# TDA5340.net
KiCad netlist of a schematic drawn in Altium Designer
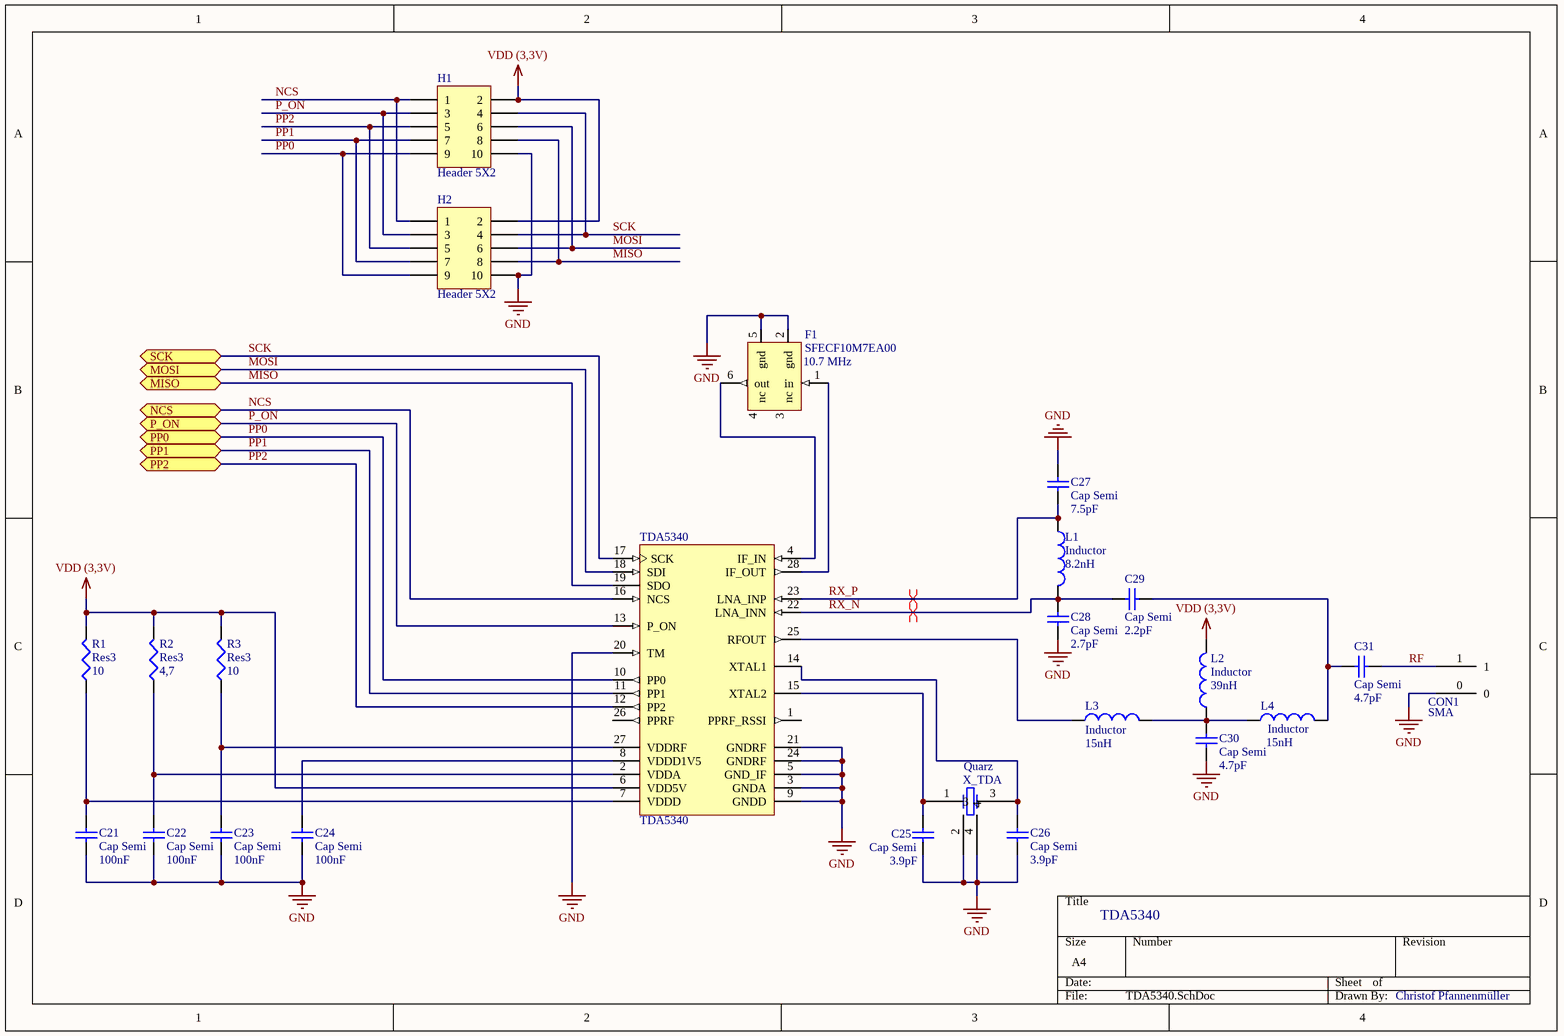
[diagram p0: TDA5340.SchDoc]

(export (version "E")
  (design (tool "Eeschema 10.0.6"))
  (components
    (comp (ref "C21")
      (value "Cap Semi")
      (footprint "0402")
      (description "Capacitor (Semiconductor SIM Model)")
      (fields (field (name "ALTIUM_VALUE") "100nF") (field (name "PUBLISHER") "Altium Limited"))
      (libsource (lib "Miscellaneous Devices") (part "Cap Semi"))
    )
    (comp (ref "C22")
      (value "Cap Semi")
      (footprint "0402")
      (description "Capacitor (Semiconductor SIM Model)")
      (fields (field (name "ALTIUM_VALUE") "100nF") (field (name "PUBLISHER") "Altium Limited"))
      (libsource (lib "Miscellaneous Devices") (part "Cap Semi"))
    )
    (comp (ref "C23")
      (value "Cap Semi")
      (footprint "0402")
      (description "Capacitor (Semiconductor SIM Model)")
      (fields (field (name "ALTIUM_VALUE") "100nF") (field (name "PUBLISHER") "Altium Limited"))
      (libsource (lib "Miscellaneous Devices") (part "Cap Semi"))
    )
    (comp (ref "C24")
      (value "Cap Semi")
      (footprint "0402")
      (description "Capacitor (Semiconductor SIM Model)")
      (fields (field (name "ALTIUM_VALUE") "100nF") (field (name "PUBLISHER") "Altium Limited"))
      (libsource (lib "Miscellaneous Devices") (part "Cap Semi"))
    )
    (comp (ref "C25")
      (value "Cap Semi")
      (footprint "0402")
      (description "Capacitor (Semiconductor SIM Model)")
      (fields (field (name "ALTIUM_VALUE") "3.9pF") (field (name "PUBLISHER") "Altium Limited"))
      (libsource (lib "Miscellaneous Devices") (part "Cap Semi"))
    )
    (comp (ref "C26")
      (value "Cap Semi")
      (footprint "0402")
      (description "Capacitor (Semiconductor SIM Model)")
      (fields (field (name "ALTIUM_VALUE") "3.9pF") (field (name "PUBLISHER") "Altium Limited"))
      (libsource (lib "Miscellaneous Devices") (part "Cap Semi"))
    )
    (comp (ref "C27")
      (value "Cap Semi")
      (footprint "0402")
      (description "Capacitor (Semiconductor SIM Model)")
      (fields (field (name "ALTIUM_VALUE") "7.5pF") (field (name "PUBLISHER") "Altium Limited"))
      (libsource (lib "Miscellaneous Devices") (part "Cap Semi"))
    )
    (comp (ref "C28")
      (value "Cap Semi")
      (footprint "0402")
      (description "Capacitor (Semiconductor SIM Model)")
      (fields (field (name "ALTIUM_VALUE") "2.7pF") (field (name "PUBLISHER") "Altium Limited"))
      (libsource (lib "Miscellaneous Devices") (part "Cap Semi"))
    )
    (comp (ref "C29")
      (value "Cap Semi")
      (footprint "0402")
      (description "Capacitor (Semiconductor SIM Model)")
      (fields (field (name "ALTIUM_VALUE") "2.2pF") (field (name "PUBLISHER") "Altium Limited"))
      (libsource (lib "Miscellaneous Devices") (part "Cap Semi"))
    )
    (comp (ref "C30")
      (value "Cap Semi")
      (footprint "0402")
      (description "Capacitor (Semiconductor SIM Model)")
      (fields (field (name "ALTIUM_VALUE") "4.7pF") (field (name "PUBLISHER") "Altium Limited"))
      (libsource (lib "Miscellaneous Devices") (part "Cap Semi"))
    )
    (comp (ref "C31")
      (value "Cap Semi")
      (footprint "0402")
      (description "Capacitor (Semiconductor SIM Model)")
      (fields (field (name "ALTIUM_VALUE") "4.7pF") (field (name "PUBLISHER") "Altium Limited"))
      (libsource (lib "Miscellaneous Devices") (part "Cap Semi"))
    )
    (comp (ref "CON1") (value "SMA") (footprint "SMA") (libsource (lib "Schlib1_rev2") (part "SMA")))
    (comp (ref "F1")
      (value "SFECF10M7EA00")
      (footprint "SOP6")
      (fields (field (name "FREQUENZ") "10.7 MHz"))
      (libsource (lib "Schlib1") (part "SFECF10M7EA00"))
    )
    (comp (ref "H1")
      (value "Header 5X2")
      (footprint "HDR2X5")
      (description "Header, 5-Pin, Dual row")
      (fields (field (name "PUBLISHER") "Altium Limited"))
      (libsource (lib "Miscellaneous Connectors") (part "Header 5X2"))
    )
    (comp (ref "H2")
      (value "Header 5X2")
      (footprint "HDR2X5")
      (description "Header, 5-Pin, Dual row")
      (fields (field (name "PUBLISHER") "Altium Limited"))
      (libsource (lib "Miscellaneous Connectors") (part "Header 5X2"))
    )
    (comp (ref "L1")
      (value "Inductor")
      (footprint "INDC1608L")
      (fields (field (name "ALTIUM_VALUE") "8.2nH") (field (name "PUBLISHER") "Altium Limited"))
      (libsource (lib "Miscellaneous Devices") (part "Inductor"))
    )
    (comp (ref "L2")
      (value "Inductor")
      (footprint "INDC1608L")
      (fields (field (name "ALTIUM_VALUE") "39nH") (field (name "PUBLISHER") "Altium Limited"))
      (libsource (lib "Miscellaneous Devices") (part "Inductor"))
    )
    (comp (ref "L3")
      (value "Inductor")
      (footprint "INDC1608L")
      (fields (field (name "ALTIUM_VALUE") "15nH") (field (name "PUBLISHER") "Altium Limited"))
      (libsource (lib "Miscellaneous Devices") (part "Inductor"))
    )
    (comp (ref "L4")
      (value "Inductor")
      (footprint "INDC1608L")
      (fields (field (name "ALTIUM_VALUE") "15nH") (field (name "PUBLISHER") "Altium Limited"))
      (libsource (lib "Miscellaneous Devices") (part "Inductor"))
    )
    (comp (ref "R1")
      (value "Res3")
      (footprint "J1-0603")
      (description "Resistor")
      (fields (field (name "ALTIUM_VALUE") "10") (field (name "PUBLISHER") "Altium Limited"))
      (libsource (lib "Miscellaneous Devices") (part "Res3"))
    )
    (comp (ref "R2")
      (value "Res3")
      (footprint "J1-0603")
      (description "Resistor")
      (fields (field (name "ALTIUM_VALUE") "4,7") (field (name "PUBLISHER") "Altium Limited"))
      (libsource (lib "Miscellaneous Devices") (part "Res3"))
    )
    (comp (ref "R3")
      (value "Res3")
      (footprint "J1-0603")
      (description "Resistor")
      (fields (field (name "ALTIUM_VALUE") "10") (field (name "PUBLISHER") "Altium Limited"))
      (libsource (lib "Miscellaneous Devices") (part "Res3"))
    )
    (comp (ref "TDA5340")
      (value "TDA5340")
      (footprint "INF-PG-TSSOP-28_N")
      (description "High Sensitivity Multi-Channel Transceiver, -40 to 110 degC, PG-TSSOP-28, Green")
      (fields (field (name "MANUFACTURER") "Infineon"))
      (libsource (lib "TDA5340") (part "TDA5340"))
    )
    (comp (ref "X_TDA") (value "Quarz") (footprint "Quarz") (libsource (lib "Schlib1") (part "Quarz")))
  )
  (nets
    (net (code "1") (name "/MISO") (class "Default")
      (node (ref "H1") (pin "8") (pinfunction "8_8") (pintype "passive"))
      (node (ref "H2") (pin "8") (pinfunction "8_8") (pintype "passive"))
      (node (ref "TDA5340") (pin "19") (pinfunction "SDO_19") (pintype "tri_state"))
    )
    (net (code "2") (name "/MOSI") (class "Default")
      (node (ref "H1") (pin "6") (pinfunction "6_6") (pintype "passive"))
      (node (ref "H2") (pin "6") (pinfunction "6_6") (pintype "passive"))
      (node (ref "TDA5340") (pin "18") (pinfunction "SDI_18") (pintype "input"))
    )
    (net (code "3") (name "/NCS") (class "Default")
      (node (ref "H1") (pin "1") (pinfunction "1_1") (pintype "passive"))
      (node (ref "H2") (pin "1") (pinfunction "1_1") (pintype "passive"))
      (node (ref "TDA5340") (pin "16") (pinfunction "NCS_16") (pintype "input"))
    )
    (net (code "4") (name "/PP0") (class "Default")
      (node (ref "H1") (pin "9") (pinfunction "9_9") (pintype "passive"))
      (node (ref "H2") (pin "9") (pinfunction "9_9") (pintype "passive"))
      (node (ref "TDA5340") (pin "10") (pinfunction "PP0_10") (pintype "output"))
    )
    (net (code "5") (name "/PP1") (class "Default")
      (node (ref "H1") (pin "7") (pinfunction "7_7") (pintype "passive"))
      (node (ref "H2") (pin "7") (pinfunction "7_7") (pintype "passive"))
      (node (ref "TDA5340") (pin "11") (pinfunction "PP1_11") (pintype "output"))
    )
    (net (code "6") (name "/PP2") (class "Default")
      (node (ref "H1") (pin "5") (pinfunction "5_5") (pintype "passive"))
      (node (ref "H2") (pin "5") (pinfunction "5_5") (pintype "passive"))
      (node (ref "TDA5340") (pin "12") (pinfunction "PP2_12") (pintype "output"))
    )
    (net (code "7") (name "/P_ON") (class "Default")
      (node (ref "H1") (pin "3") (pinfunction "3_3") (pintype "passive"))
      (node (ref "H2") (pin "3") (pinfunction "3_3") (pintype "passive"))
      (node (ref "TDA5340") (pin "13") (pinfunction "P_ON_13") (pintype "input"))
    )
    (net (code "8") (name "/RF") (class "Default")
      (node (ref "C31") (pin "2") (pinfunction "2_2") (pintype "passive"))
      (node (ref "CON1") (pin "1") (pinfunction "1_1") (pintype "passive"))
    )
    (net (code "9") (name "/RX_N") (class "Default")
      (node (ref "C28") (pin "1") (pinfunction "1_1") (pintype "passive"))
      (node (ref "C29") (pin "2") (pinfunction "2_2") (pintype "passive"))
      (node (ref "L1") (pin "2") (pinfunction "2_2") (pintype "passive"))
      (node (ref "TDA5340") (pin "22") (pinfunction "LNA_INN_22") (pintype "input"))
    )
    (net (code "10") (name "/RX_P") (class "Default")
      (node (ref "C27") (pin "2") (pinfunction "2_2") (pintype "passive"))
      (node (ref "L1") (pin "1") (pinfunction "1_1") (pintype "passive"))
      (node (ref "TDA5340") (pin "23") (pinfunction "LNA_INP_23") (pintype "input"))
    )
    (net (code "11") (name "/SCK") (class "Default")
      (node (ref "H1") (pin "4") (pinfunction "4_4") (pintype "passive"))
      (node (ref "H2") (pin "4") (pinfunction "4_4") (pintype "passive"))
      (node (ref "TDA5340") (pin "17") (pinfunction "SCK_17") (pintype "input"))
    )
    (net (code "12") (name "GND") (class "Default")
      (node (ref "C21") (pin "2") (pinfunction "2_2") (pintype "passive"))
      (node (ref "C22") (pin "2") (pinfunction "2_2") (pintype "passive"))
      (node (ref "C23") (pin "2") (pinfunction "2_2") (pintype "passive"))
      (node (ref "C24") (pin "2") (pinfunction "2_2") (pintype "passive"))
      (node (ref "C25") (pin "2") (pinfunction "2_2") (pintype "passive"))
      (node (ref "C26") (pin "1") (pinfunction "1_1") (pintype "passive"))
      (node (ref "C27") (pin "1") (pinfunction "1_1") (pintype "passive"))
      (node (ref "C28") (pin "2") (pinfunction "2_2") (pintype "passive"))
      (node (ref "C30") (pin "1") (pinfunction "1_1") (pintype "passive"))
      (node (ref "CON1") (pin "0") (pinfunction "0_0") (pintype "passive"))
      (node (ref "F1") (pin "2") (pinfunction "gnd_2") (pintype "power_in"))
      (node (ref "F1") (pin "5") (pinfunction "gnd_5") (pintype "passive"))
      (node (ref "H1") (pin "10") (pinfunction "10_10") (pintype "passive"))
      (node (ref "H2") (pin "10") (pinfunction "10_10") (pintype "passive"))
      (node (ref "TDA5340") (pin "20") (pinfunction "TM_20") (pintype "input"))
      (node (ref "TDA5340") (pin "21") (pinfunction "GNDRF_21") (pintype "power_in"))
      (node (ref "TDA5340") (pin "24") (pinfunction "GNDRF_24") (pintype "power_in"))
      (node (ref "TDA5340") (pin "3") (pinfunction "GNDA_3") (pintype "power_in"))
      (node (ref "TDA5340") (pin "5") (pinfunction "GND_IF_5") (pintype "power_in"))
      (node (ref "TDA5340") (pin "9") (pinfunction "GNDD_9") (pintype "power_in"))
      (node (ref "X_TDA") (pin "2") (pinfunction "2_2") (pintype "passive"))
      (node (ref "X_TDA") (pin "4") (pinfunction "4_4") (pintype "passive"))
    )
    (net (code "13") (name "Net-(C29-Pad1)") (class "Default")
      (node (ref "C29") (pin "1") (pinfunction "1_1") (pintype "passive"))
      (node (ref "C31") (pin "1") (pinfunction "1_1") (pintype "passive"))
      (node (ref "L4") (pin "2") (pinfunction "2_2") (pintype "passive"))
    )
    (net (code "14") (name "Net-(C30-Pad2)") (class "Default")
      (node (ref "C30") (pin "2") (pinfunction "2_2") (pintype "passive"))
      (node (ref "L2") (pin "1") (pinfunction "1_1") (pintype "passive"))
      (node (ref "L3") (pin "2") (pinfunction "2_2") (pintype "passive"))
      (node (ref "L4") (pin "1") (pinfunction "1_1") (pintype "passive"))
    )
    (net (code "15") (name "Net-(F1-in)") (class "Default")
      (node (ref "F1") (pin "1") (pinfunction "in_1") (pintype "input"))
      (node (ref "TDA5340") (pin "28") (pinfunction "IF_OUT_28") (pintype "output"))
    )
    (net (code "16") (name "Net-(F1-out)") (class "Default")
      (node (ref "F1") (pin "6") (pinfunction "out_6") (pintype "output"))
      (node (ref "TDA5340") (pin "4") (pinfunction "IF_IN_4") (pintype "input"))
    )
    (net (code "17") (name "Net-(TDA5340-RFOUT)") (class "Default")
      (node (ref "L3") (pin "1") (pinfunction "1_1") (pintype "passive"))
      (node (ref "TDA5340") (pin "25") (pinfunction "RFOUT_25") (pintype "output"))
    )
    (net (code "18") (name "Net-(TDA5340-VDDA)") (class "Default")
      (node (ref "C22") (pin "1") (pinfunction "1_1") (pintype "passive"))
      (node (ref "R2") (pin "1") (pinfunction "1_1") (pintype "passive"))
      (node (ref "TDA5340") (pin "2") (pinfunction "VDDA_2") (pintype "power_in"))
    )
    (net (code "19") (name "Net-(TDA5340-VDDD)") (class "Default")
      (node (ref "C21") (pin "1") (pinfunction "1_1") (pintype "passive"))
      (node (ref "R1") (pin "1") (pinfunction "1_1") (pintype "passive"))
      (node (ref "TDA5340") (pin "7") (pinfunction "VDDD_7") (pintype "power_in"))
    )
    (net (code "20") (name "Net-(TDA5340-VDDD1V5)") (class "Default")
      (node (ref "C24") (pin "1") (pinfunction "1_1") (pintype "passive"))
      (node (ref "TDA5340") (pin "8") (pinfunction "VDDD1V5_8") (pintype "power_in"))
    )
    (net (code "21") (name "Net-(TDA5340-VDDRF)") (class "Default")
      (node (ref "C23") (pin "1") (pinfunction "1_1") (pintype "passive"))
      (node (ref "R3") (pin "1") (pinfunction "1_1") (pintype "passive"))
      (node (ref "TDA5340") (pin "27") (pinfunction "VDDRF_27") (pintype "power_in"))
    )
    (net (code "22") (name "Net-(TDA5340-XTAL1)") (class "Default")
      (node (ref "C26") (pin "2") (pinfunction "2_2") (pintype "passive"))
      (node (ref "TDA5340") (pin "14") (pinfunction "XTAL1_14") (pintype "passive"))
      (node (ref "X_TDA") (pin "3") (pinfunction "3_3") (pintype "passive"))
    )
    (net (code "23") (name "Net-(TDA5340-XTAL2)") (class "Default")
      (node (ref "C25") (pin "1") (pinfunction "1_1") (pintype "passive"))
      (node (ref "TDA5340") (pin "15") (pinfunction "XTAL2_15") (pintype "passive"))
      (node (ref "X_TDA") (pin "1") (pinfunction "1_1") (pintype "passive"))
    )
    (net (code "24") (name "VDD (3,3V)") (class "Default")
      (node (ref "H1") (pin "2") (pinfunction "2_2") (pintype "passive"))
      (node (ref "H2") (pin "2") (pinfunction "2_2") (pintype "passive"))
      (node (ref "L2") (pin "2") (pinfunction "2_2") (pintype "passive"))
      (node (ref "R1") (pin "2") (pinfunction "2_2") (pintype "passive"))
      (node (ref "R2") (pin "2") (pinfunction "2_2") (pintype "passive"))
      (node (ref "R3") (pin "2") (pinfunction "2_2") (pintype "passive"))
      (node (ref "TDA5340") (pin "6") (pinfunction "VDD5V_6") (pintype "power_in"))
    )
    (net (code "25") (name "unconnected-(F1-nc-Pad3)") (class "Default")
      (node (ref "F1") (pin "3") (pinfunction "nc_3") (pintype "passive"))
    )
    (net (code "26") (name "unconnected-(F1-nc-Pad4)") (class "Default")
      (node (ref "F1") (pin "4") (pinfunction "nc_4") (pintype "passive"))
    )
    (net (code "27") (name "unconnected-(TDA5340-PPRF-Pad26)") (class "Default")
      (node (ref "TDA5340") (pin "26") (pinfunction "PPRF_26") (pintype "output"))
    )
    (net (code "28") (name "unconnected-(TDA5340-PPRF_RSSI-Pad1)") (class "Default")
      (node (ref "TDA5340") (pin "1") (pinfunction "PPRF_RSSI_1") (pintype "output"))
    )
  )
)
